# altium.net
KiCad netlist of a schematic drawn in Altium Designer
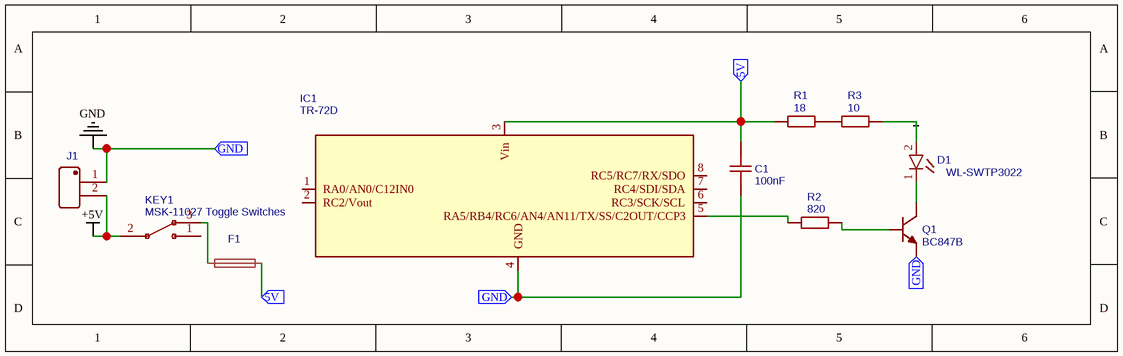
[diagram p0: altium.schdoc]

(export (version "E")
  (design (tool "Eeschema 10.0.6"))
  (components
    (comp (ref "C1")
      (value "100nF")
      (fields
        (field (name "BOM_SUPPLIER PART") "C304011")
        (field (name "BOM_MANUFACTURER PART") "1210B106K100CT")
        (field (name "CONTRIBUTOR") "LCSC")
      )
      (libsource (lib "altium-import") (part "root_3_100nF_"))
    )
    (comp (ref "D1")
      (value "WL-SWTP3022")
      (description "WL-SWTP")
      (libsource (lib "altium-import") (part "root_3_WL-SWTP3022_"))
    )
    (comp (ref "F1")
      (value "NO")
      (fields
        (field (name "BOM_MANUFACTURER PART") "3403.0015.11")
        (field (name "BOM_SUPPLIER PART") "693-3403.0015.11")
        (field (name "CONTRIBUTOR") "romiksm")
      )
      (libsource (lib "altium-import") (part "root_0_NO_"))
    )
    (comp (ref "IC1")
      (value "TR-72D")
      (fields (field (name "CONTRIBUTOR") "Simen Stensas"))
      (libsource (lib "altium-import") (part "root_0_TR-72D_"))
    )
    (comp (ref "J1")
      (value "KF127_2P_5.08")
      (fields (field (name "BOM_MANUFACTURER PART") "KF127L-5.08") (field (name "CONTRIBUTOR") "GrahamG"))
      (libsource (lib "altium-import") (part "root_0_KF127_2P_5.08_"))
    )
    (comp (ref "KEY1")
      (value "MSK-11027 Toggle Switches")
      (fields (field (name "BOM_SUPPLIER PART") "C21381"))
      (libsource (lib "altium-import") (part "root_0_MSK-11027 Toggle Switches_"))
    )
    (comp (ref "Q1")
      (value "BC847B")
      (fields (field (name "BOM_SUPPLIER PART") "C181140") (field (name "CONTRIBUTOR") "LCSC"))
      (libsource (lib "altium-import") (part "root_0_BC847B_"))
    )
    (comp (ref "R1")
      (value "18")
      (fields
        (field (name "BOM_SUPPLIER PART") "C204720")
        (field (name "BOM_MANUFACTURER PART") "CR1206-FX-18R0ELF")
        (field (name "CONTRIBUTOR") "LCSC")
      )
      (libsource (lib "altium-import") (part "root_0_18_"))
    )
    (comp (ref "R2")
      (value "820")
      (fields
        (field (name "BOM_SUPPLIER PART") "C352031")
        (field (name "BOM_MANUFACTURER PART") "AECR1206F820RK9")
        (field (name "CONTRIBUTOR") "LCSC")
      )
      (libsource (lib "altium-import") (part "root_0_820_"))
    )
    (comp (ref "R3")
      (value "10")
      (fields
        (field (name "BOM_SUPPLIER PART") "C352161")
        (field (name "BOM_MANUFACTURER PART") "AECR1206F10R0K9")
        (field (name "CONTRIBUTOR") "LCSC")
      )
      (libsource (lib "altium-import") (part "root_0_10_"))
    )
  )
  (nets
    (net (code "1") (name "+5V") (class "Default")
      (node (ref "J1") (pin "2") (pinfunction "PIN2_2") (pintype "passive"))
      (node (ref "KEY1") (pin "2") (pinfunction "2_2") (pintype "passive"))
    )
    (net (code "2") (name "/5V") (class "Default")
      (node (ref "C1") (pin "2") (pinfunction "2_2") (pintype "passive"))
      (node (ref "F1") (pin "2") (pinfunction "2_2") (pintype "passive"))
      (node (ref "IC1") (pin "3") (pinfunction "Vin_3") (pintype "passive"))
      (node (ref "R1") (pin "1") (pinfunction "1_1") (pintype "passive"))
    )
    (net (code "3") (name "GND") (class "Default")
      (node (ref "C1") (pin "1") (pinfunction "1_1") (pintype "passive"))
      (node (ref "IC1") (pin "4") (pinfunction "GND_4") (pintype "passive"))
      (node (ref "J1") (pin "1") (pinfunction "PIN1_1") (pintype "passive"))
      (node (ref "Q1") (pin "2") (pinfunction "E_2") (pintype "passive"))
    )
    (net (code "4") (name "Net-(D1-Pad2)") (class "Default")
      (node (ref "D1") (pin "2") (pinfunction "2_2") (pintype "passive"))
      (node (ref "R3") (pin "2") (pinfunction "2_2") (pintype "passive"))
    )
    (net (code "5") (name "Net-(F1-Pad1)") (class "Default")
      (node (ref "F1") (pin "1") (pinfunction "1_1") (pintype "passive"))
      (node (ref "KEY1") (pin "3") (pinfunction "3_3") (pintype "passive"))
    )
    (net (code "6") (name "Net-(IC1-RA5{slash}RB4{slash}RC6{slash}AN4{slash}AN11{slash}TX{slash}SS{slash}C2OUT{slash}CCP3)") (class "Default")
      (node (ref "IC1") (pin "5") (pinfunction "RA5/RB4/RC6/AN4/AN11/TX/SS/C2OUT/CCP3_5") (pintype "passive"))
      (node (ref "R2") (pin "1") (pinfunction "1_1") (pintype "passive"))
    )
    (net (code "7") (name "Net-(Q1-B)") (class "Default")
      (node (ref "Q1") (pin "1") (pinfunction "B_1") (pintype "passive"))
      (node (ref "R2") (pin "2") (pinfunction "2_2") (pintype "passive"))
    )
    (net (code "8") (name "Net-(Q1-C)") (class "Default")
      (node (ref "D1") (pin "1") (pinfunction "1_1") (pintype "passive"))
      (node (ref "Q1") (pin "3") (pinfunction "C_3") (pintype "passive"))
    )
    (net (code "9") (name "Net-(R1-Pad2)") (class "Default")
      (node (ref "R1") (pin "2") (pinfunction "2_2") (pintype "passive"))
      (node (ref "R3") (pin "1") (pinfunction "1_1") (pintype "passive"))
    )
    (net (code "10") (name "unconnected-(IC1-RA0{slash}AN0{slash}C12IN0-Pad1)") (class "Default")
      (node (ref "IC1") (pin "1") (pinfunction "RA0/AN0/C12IN0_1") (pintype "passive"))
    )
    (net (code "11") (name "unconnected-(IC1-RC2{slash}Vout-Pad2)") (class "Default")
      (node (ref "IC1") (pin "2") (pinfunction "RC2/Vout_2") (pintype "passive"))
    )
    (net (code "12") (name "unconnected-(IC1-RC3{slash}SCK{slash}SCL-Pad6)") (class "Default")
      (node (ref "IC1") (pin "6") (pinfunction "RC3/SCK/SCL_6") (pintype "passive"))
    )
    (net (code "13") (name "unconnected-(IC1-RC4{slash}SDI{slash}SDA-Pad7)") (class "Default")
      (node (ref "IC1") (pin "7") (pinfunction "RC4/SDI/SDA_7") (pintype "passive"))
    )
    (net (code "14") (name "unconnected-(IC1-RC5{slash}RC7{slash}RX{slash}SDO-Pad8)") (class "Default")
      (node (ref "IC1") (pin "8") (pinfunction "RC5/RC7/RX/SDO_8") (pintype "passive"))
    )
    (net (code "15") (name "unconnected-(KEY1-Pad1)") (class "Default")
      (node (ref "KEY1") (pin "1") (pinfunction "1_1") (pintype "passive"))
    )
  )
)
